# MQ-2_v2_SCH.net
KiCad netlist of a schematic drawn in Altium Designer
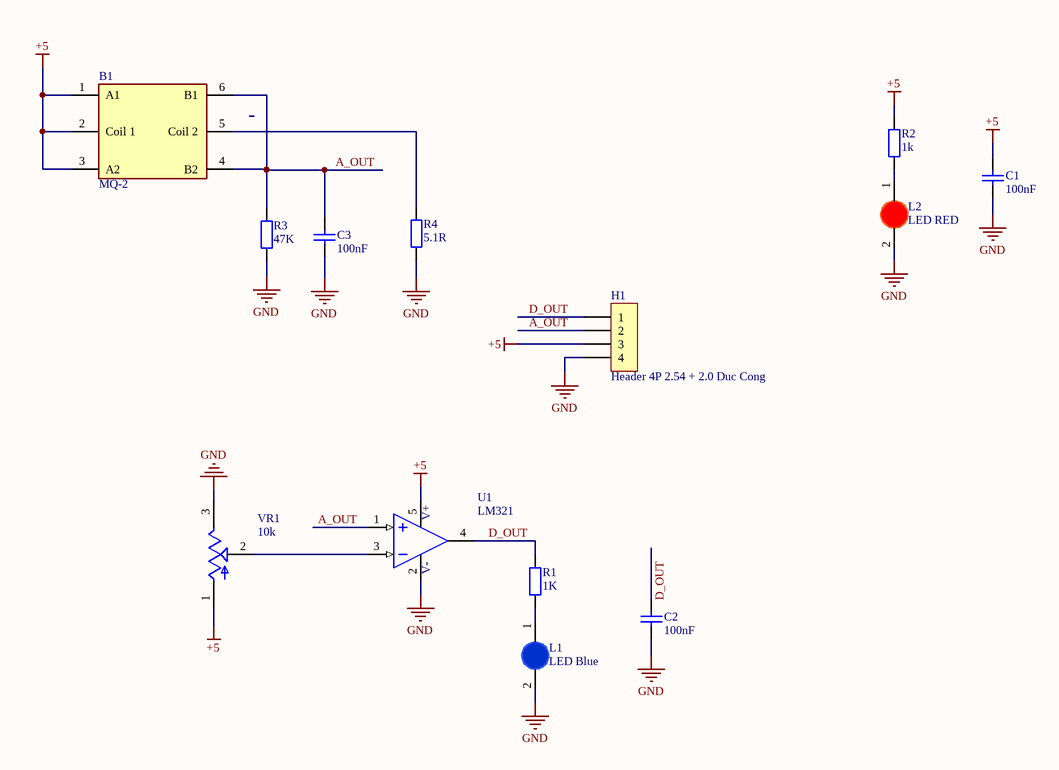
[diagram p0: MQ-2_v2_SCH.SchDoc]

(export (version "E")
  (design (tool "Eeschema 10.0.6"))
  (components
    (comp (ref "B1")
      (value "MQ-2")
      (footprint "MQ2")
      (description "Sensor: gas; smoke,combustible gases; Range: 30010000ppm; MQ-2")
      (libsource (lib "namnt_Lib") (part "MQ-2"))
    )
    (comp (ref "C1")
      (value "100nF")
      (footprint "tu 0603")
      (description "Dán")
      (libsource (lib "namnt_Lib") (part "Tu 0603 104 50V 10%"))
    )
    (comp (ref "C2")
      (value "100nF")
      (footprint "tu 0603")
      (description "Dán")
      (libsource (lib "namnt_Lib") (part "Tu 0603 104 50V 10%"))
    )
    (comp (ref "C3")
      (value "100nF")
      (footprint "tu 0603")
      (description "Dán")
      (libsource (lib "namnt_Lib") (part "Tu 0603 104 50V 10%"))
    )
    (comp (ref "H1")
      (value "Header 4P 2.54 + 2.0 Duc Cong")
      (footprint "Header 4P DC 2.54 + 2.0")
      (description "Cắm")
      (libsource (lib "namnt_Lib") (part "Header 4P 2.54 + 2.0 Duc Cong"))
    )
    (comp (ref "L1")
      (value "LED Blue")
      (footprint "LED-0805-Blue")
      (description "Dán")
      (libsource (lib "namnt_Lib") (part "LED 0805 Xanh Duong"))
    )
    (comp (ref "L2")
      (value "LED RED")
      (footprint "LED-0805-Red")
      (description "Dán")
      (libsource (lib "namnt_Lib") (part "LED 0805 Do"))
    )
    (comp (ref "R1")
      (value "1K")
      (footprint "tro smd 0603")
      (description "Dán")
      (libsource (lib "namnt_Lib") (part "Tro 0603 1% 1k"))
    )
    (comp (ref "R2")
      (value "1k")
      (footprint "tro smd 0603")
      (description "Dán")
      (libsource (lib "namnt_Lib") (part "Tro 0603 1% 1k"))
    )
    (comp (ref "R3")
      (value "47K")
      (footprint "tro smd 0603")
      (description "Dán")
      (libsource (lib "namnt_Lib") (part "Tro 0603 5% 47k"))
    )
    (comp (ref "R4")
      (value "5.1R")
      (footprint "tro smd 0603")
      (description "Dán")
      (libsource (lib "namnt_Lib") (part "Tro 0603 5% 47k"))
    )
    (comp (ref "U1")
      (value "LM321")
      (footprint "xlib:sot23-5")
      (description "Opamp")
      (libsource (lib "XLib") (part "LM321"))
    )
    (comp (ref "VR1")
      (value "10k")
      (footprint "TRIM_3362P-1-102")
      (description "TRIMMER - 1/4in SQ ST CERMET ¦ Bourns 3362P-1-102")
      (fields (field (name "MF") "Bourns") (field (name "MP") "3362P-1-102"))
      (libsource (lib "namnt_Lib") (part "Bien tro vuong"))
    )
  )
  (nets
    (net (code "1") (name "+5") (class "Default")
      (node (ref "B1") (pin "1") (pinfunction "A1_1") (pintype "passive"))
      (node (ref "B1") (pin "2") (pinfunction "Coil_1_2") (pintype "passive"))
      (node (ref "B1") (pin "3") (pinfunction "A2_3") (pintype "passive"))
      (node (ref "C1") (pin "1") (pinfunction "1_1") (pintype "passive"))
      (node (ref "H1") (pin "3") (pinfunction "3_3") (pintype "passive"))
      (node (ref "R2") (pin "2") (pinfunction "2_2") (pintype "passive"))
      (node (ref "U1") (pin "5") (pinfunction "V+_5") (pintype "power_in"))
      (node (ref "VR1") (pin "1") (pinfunction "CCW_1") (pintype "passive"))
    )
    (net (code "2") (name "/A_OUT") (class "Default")
      (node (ref "B1") (pin "4") (pinfunction "B2_4") (pintype "passive"))
      (node (ref "B1") (pin "6") (pinfunction "B1_6") (pintype "passive"))
      (node (ref "C3") (pin "1") (pinfunction "1_1") (pintype "passive"))
      (node (ref "H1") (pin "2") (pinfunction "2_2") (pintype "passive"))
      (node (ref "R3") (pin "2") (pinfunction "2_2") (pintype "passive"))
      (node (ref "U1") (pin "1") (pinfunction "IN+_1") (pintype "input"))
    )
    (net (code "3") (name "/D_OUT") (class "Default")
      (node (ref "C2") (pin "1") (pinfunction "1_1") (pintype "passive"))
      (node (ref "H1") (pin "1") (pinfunction "1_1") (pintype "passive"))
      (node (ref "R1") (pin "2") (pinfunction "2_2") (pintype "passive"))
      (node (ref "U1") (pin "4") (pinfunction "-V_4") (pintype "passive"))
    )
    (net (code "4") (name "GND") (class "Default")
      (node (ref "C1") (pin "2") (pinfunction "2_2") (pintype "passive"))
      (node (ref "C2") (pin "2") (pinfunction "2_2") (pintype "passive"))
      (node (ref "C3") (pin "2") (pinfunction "2_2") (pintype "passive"))
      (node (ref "H1") (pin "4") (pinfunction "4_4") (pintype "passive"))
      (node (ref "L1") (pin "2") (pinfunction "K_2") (pintype "passive"))
      (node (ref "L2") (pin "2") (pinfunction "K_2") (pintype "passive"))
      (node (ref "R3") (pin "1") (pinfunction "1_1") (pintype "passive"))
      (node (ref "R4") (pin "1") (pinfunction "1_1") (pintype "passive"))
      (node (ref "U1") (pin "2") (pinfunction "V-_2") (pintype "power_in"))
      (node (ref "VR1") (pin "3") (pinfunction "CW_3") (pintype "passive"))
    )
    (net (code "5") (name "Net-(B1-Coil_2)") (class "Default")
      (node (ref "B1") (pin "5") (pinfunction "Coil_2_5") (pintype "passive"))
      (node (ref "R4") (pin "2") (pinfunction "2_2") (pintype "passive"))
    )
    (net (code "6") (name "Net-(L1-A)") (class "Default")
      (node (ref "L1") (pin "1") (pinfunction "A_1") (pintype "passive"))
      (node (ref "R1") (pin "1") (pinfunction "1_1") (pintype "passive"))
    )
    (net (code "7") (name "Net-(L2-A)") (class "Default")
      (node (ref "L2") (pin "1") (pinfunction "A_1") (pintype "passive"))
      (node (ref "R2") (pin "1") (pinfunction "1_1") (pintype "passive"))
    )
    (net (code "8") (name "Net-(U1-IN-)") (class "Default")
      (node (ref "U1") (pin "3") (pinfunction "IN-_3") (pintype "input"))
      (node (ref "VR1") (pin "2") (pinfunction "WIPER_2") (pintype "passive"))
    )
  )
)
